# ATLAS_XP2V5_Sheet_5.net
KiCad netlist of a schematic drawn in Altium Designer
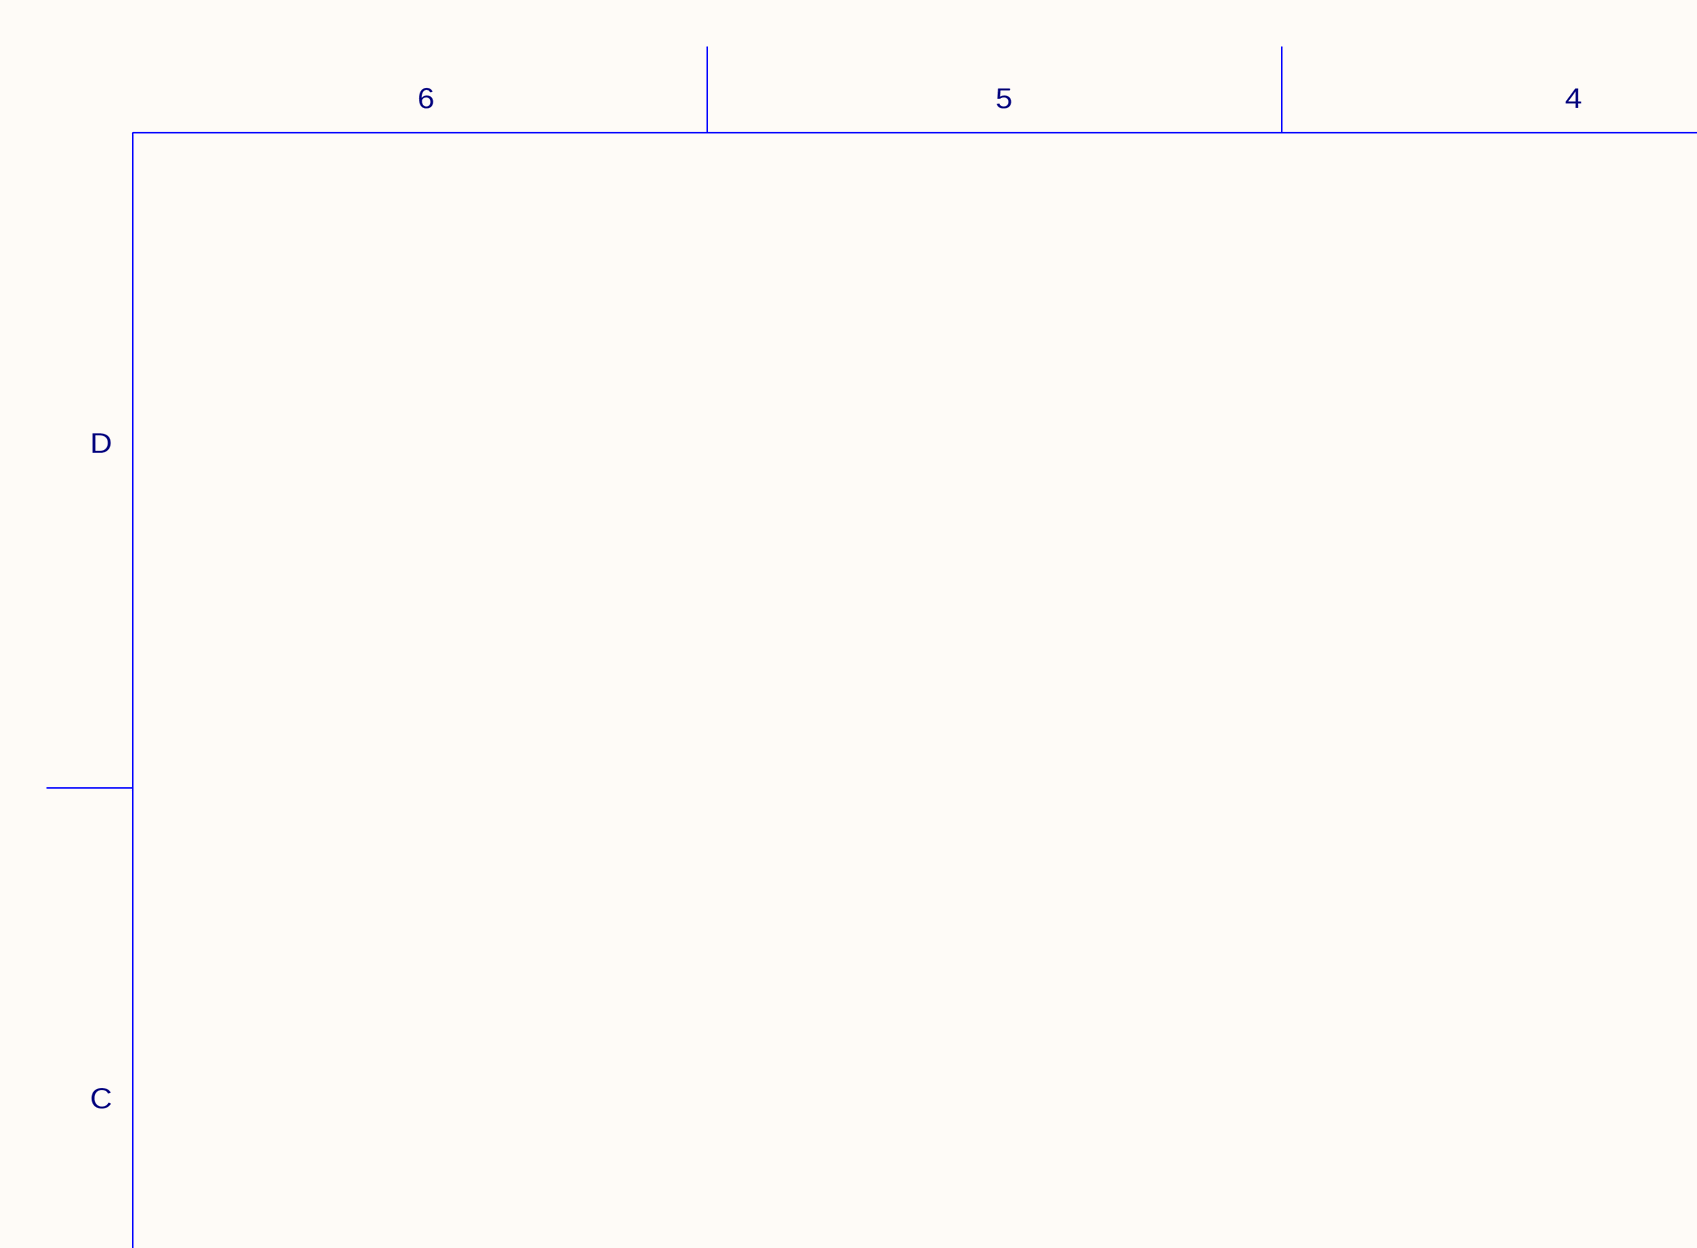
[diagram p0: ATLAS_XP2V5.Sheet 5.SchDoc, top left]
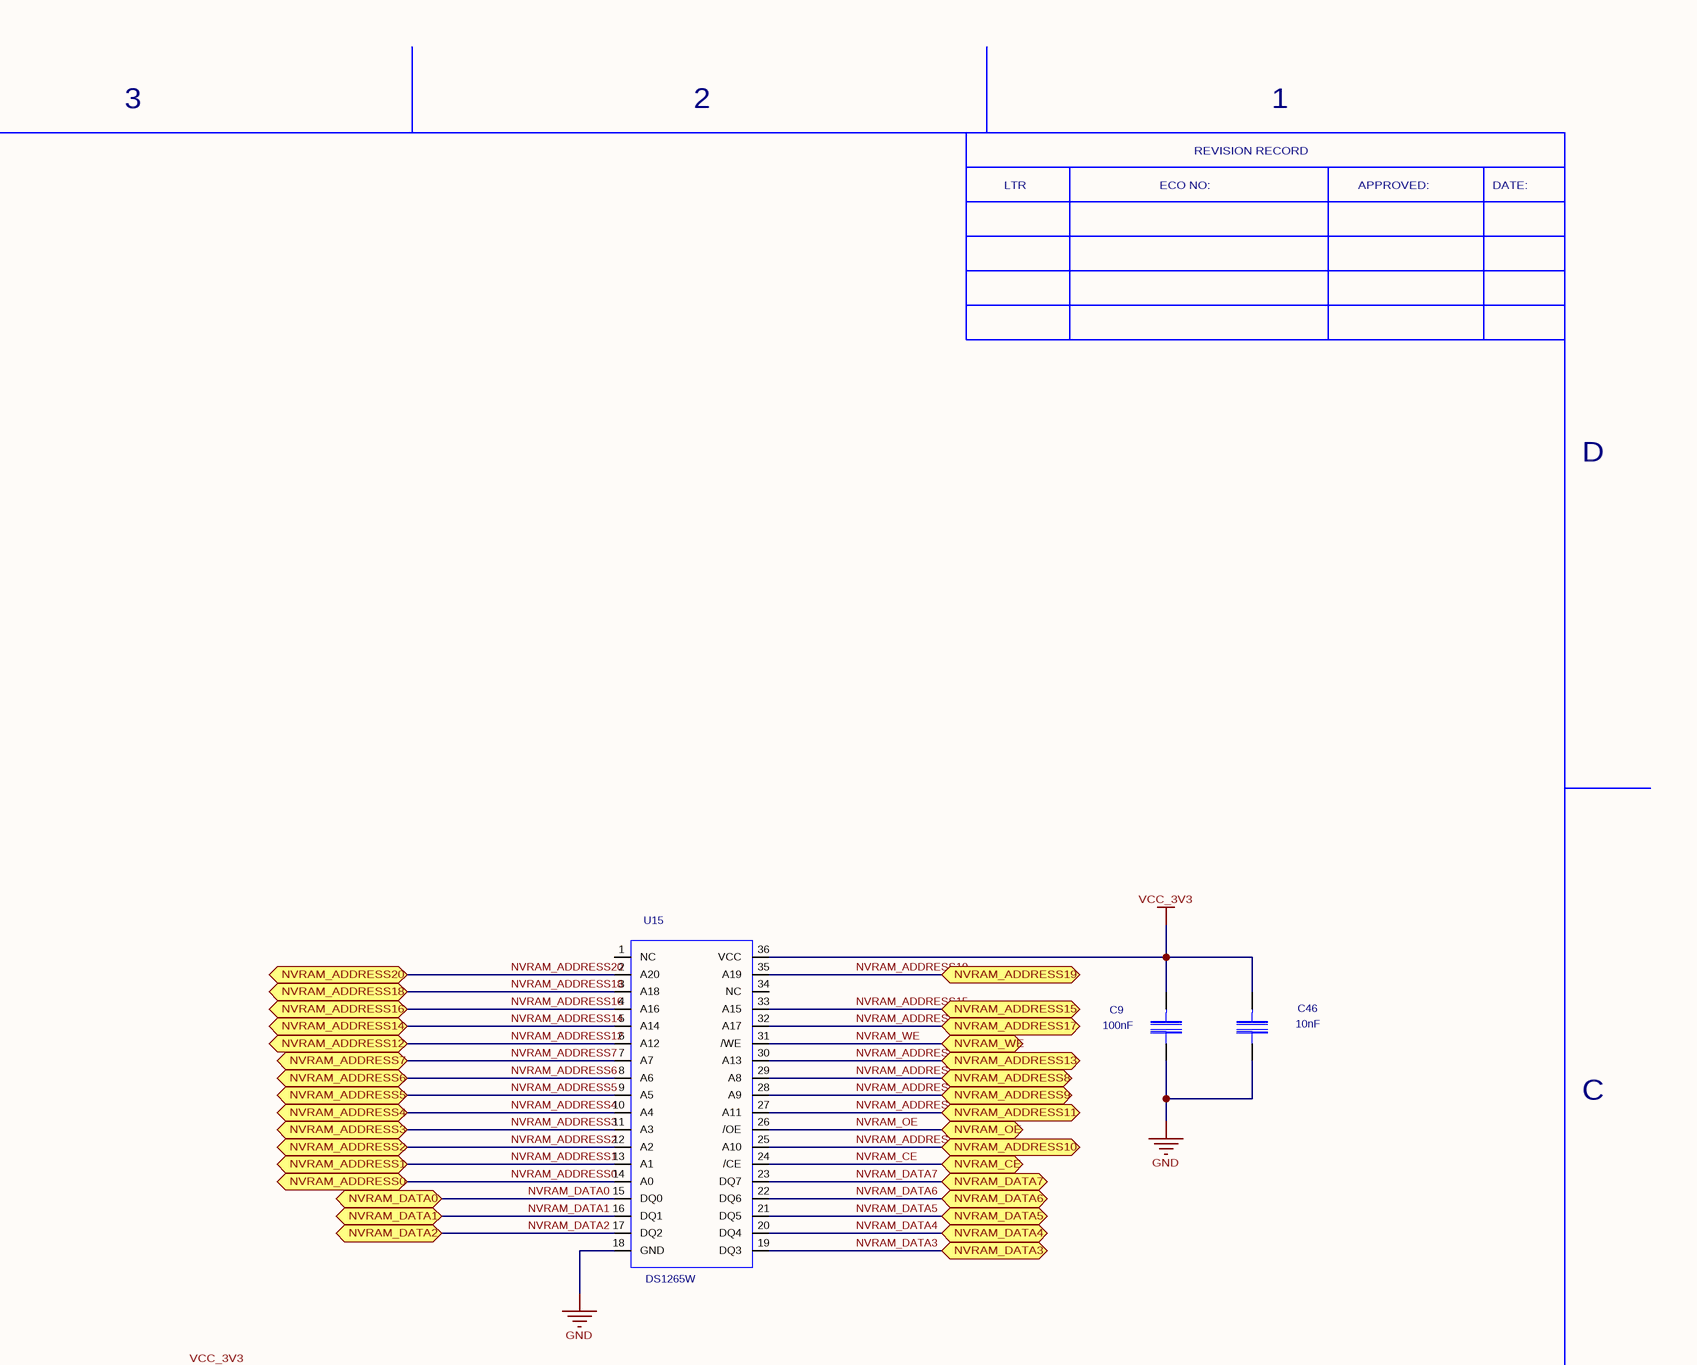
[diagram p1: ATLAS_XP2V5.Sheet 5.SchDoc, top right]
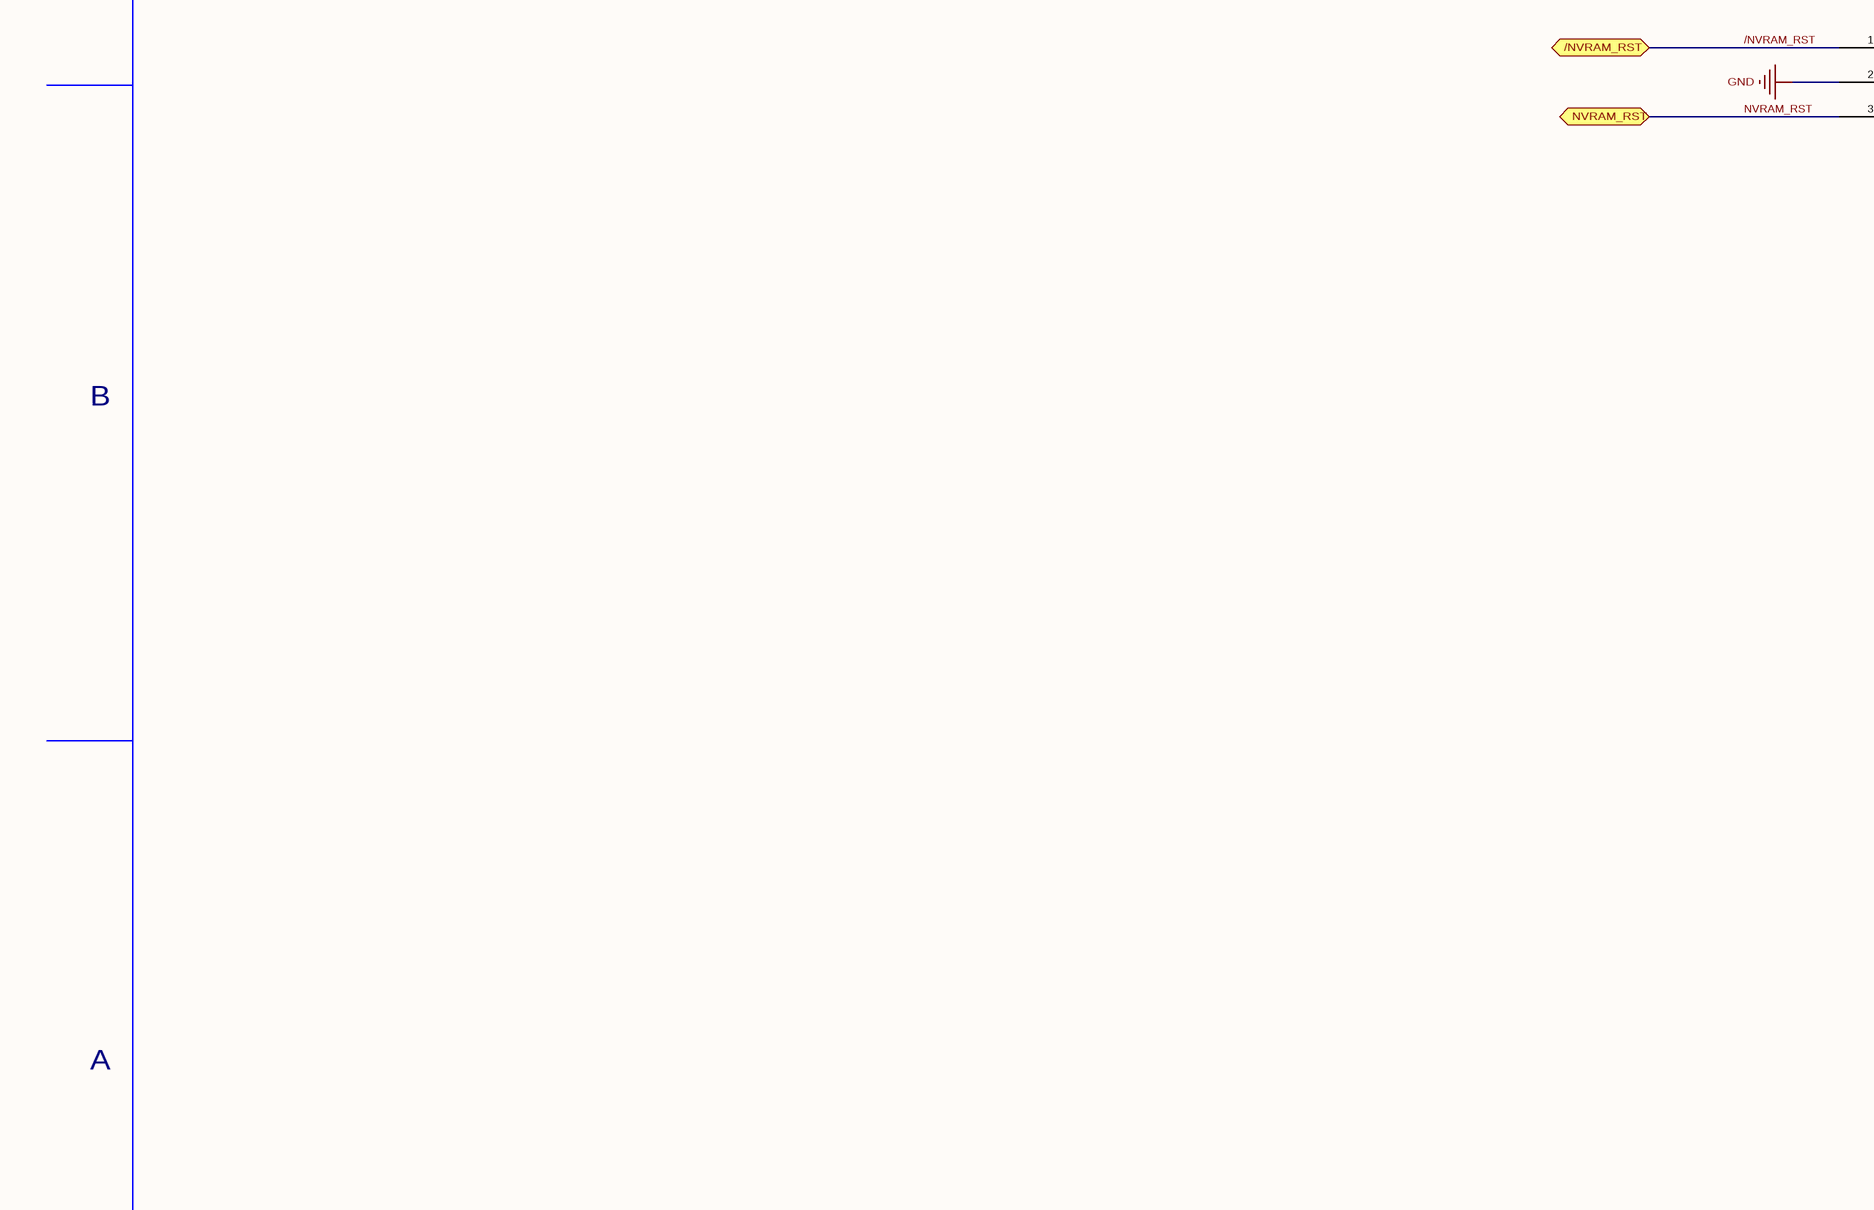
[diagram p2: ATLAS_XP2V5.Sheet 5.SchDoc, bottom left]
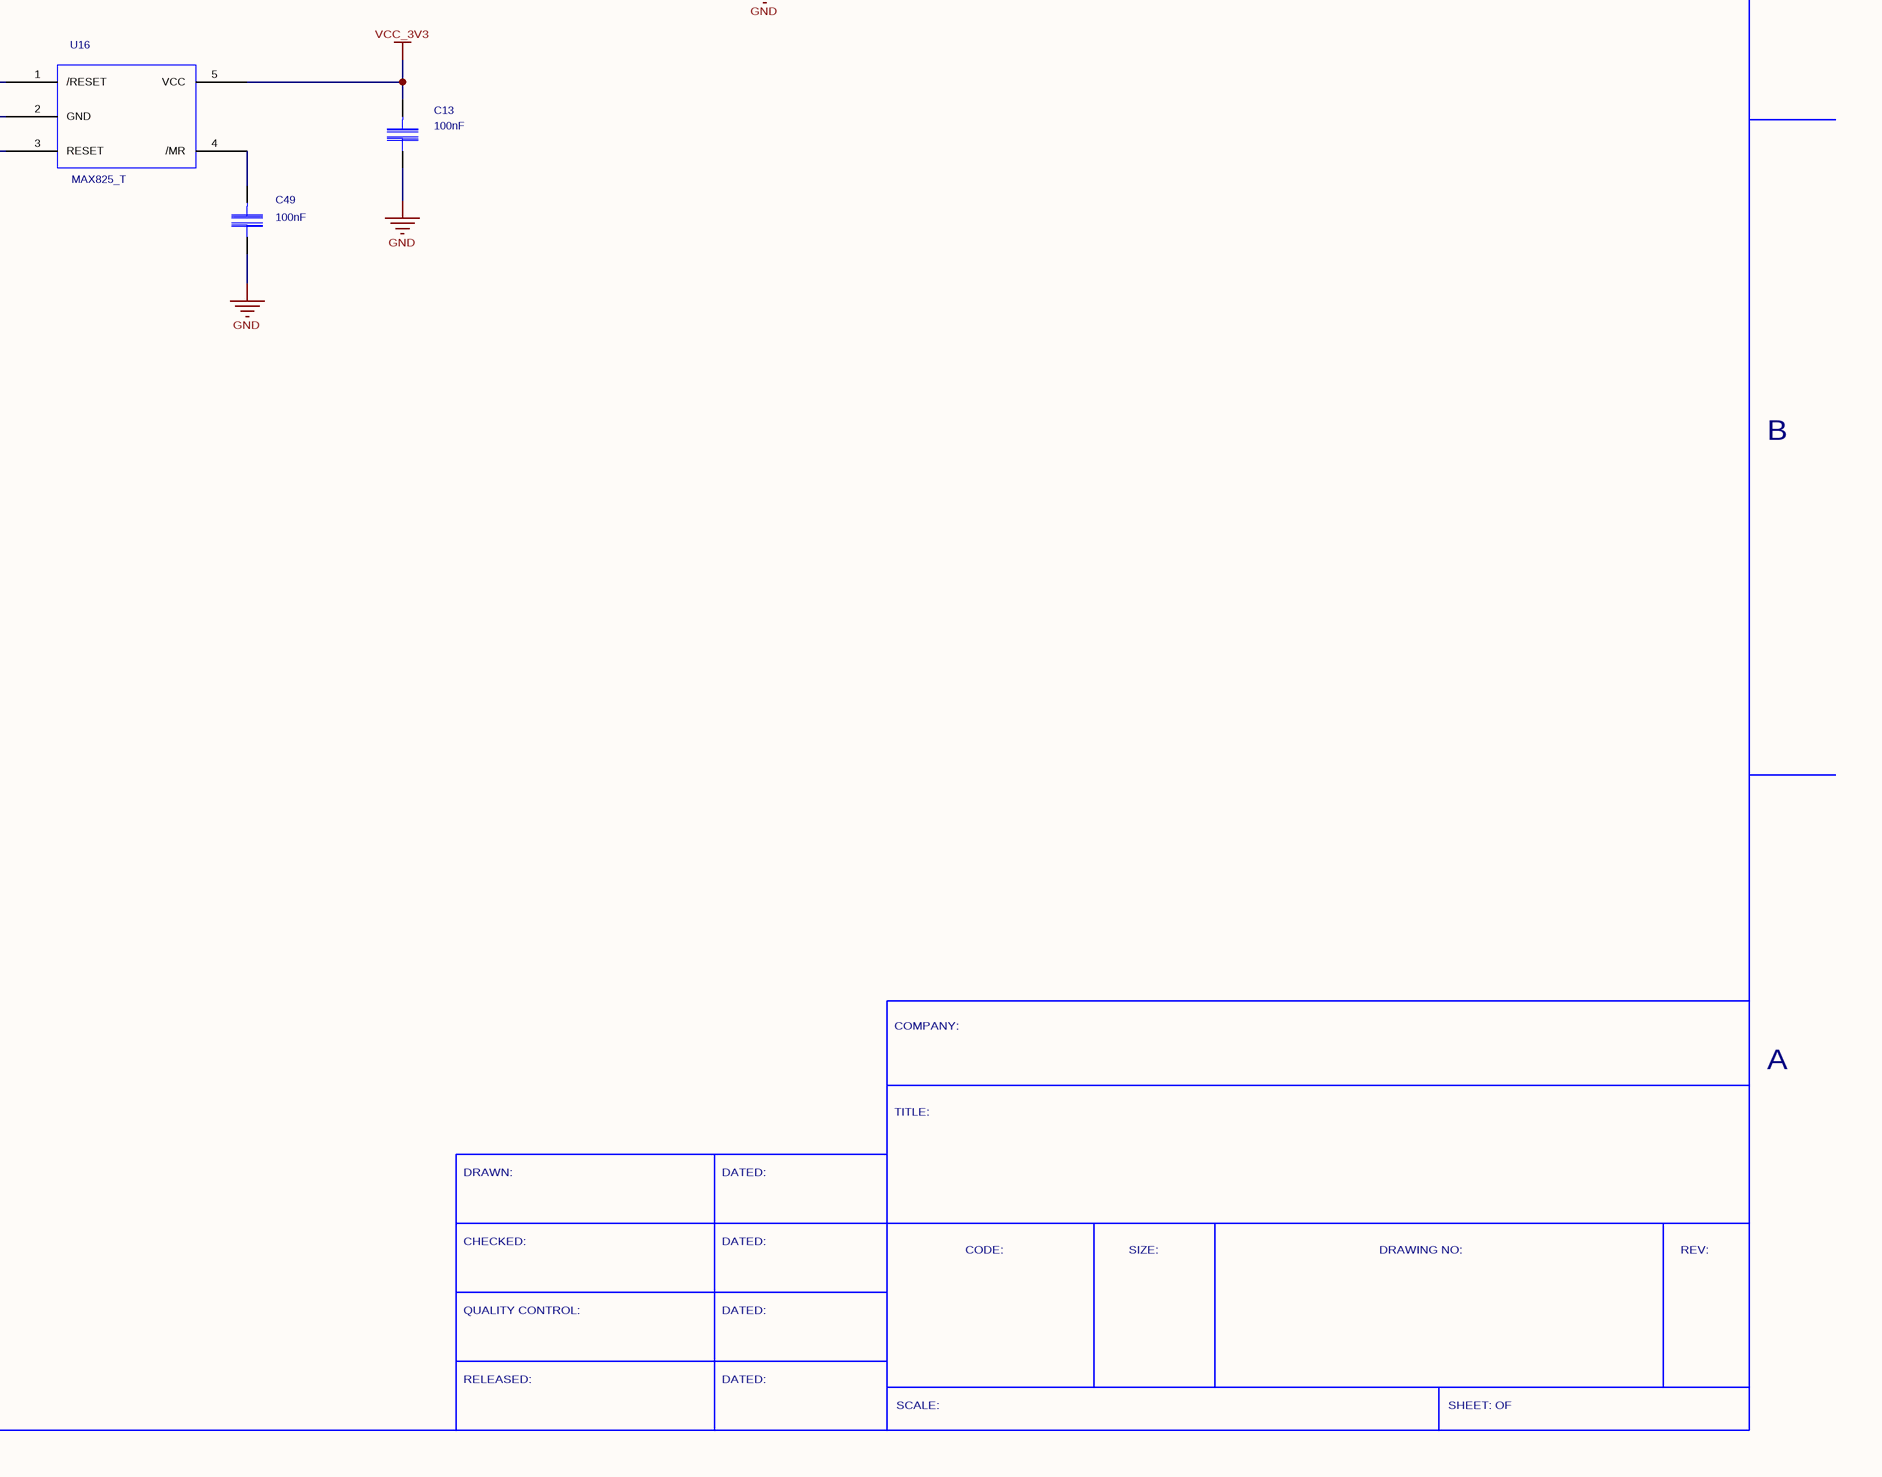
[diagram p3: ATLAS_XP2V5.Sheet 5.SchDoc, bottom right]

(export (version "E")
  (design (tool "Eeschema 10.0.6"))
  (components
    (comp (ref "C9")
      (value "100nF")
      (footprint "SM/C_0805")
      (fields (field (name "Comment") "C"))
      (libsource (lib "*") (part "C"))
    )
    (comp (ref "C13")
      (value "100nF")
      (footprint "SM/C_0805")
      (fields (field (name "Comment") "C"))
      (libsource (lib "*") (part "C"))
    )
    (comp (ref "C46")
      (value "10nF")
      (footprint "SM/C_0805")
      (fields (field (name "Comment") "C"))
      (libsource (lib "*") (part "C"))
    )
    (comp (ref "C49")
      (value "100nF")
      (footprint "SM/C_0805")
      (fields (field (name "Comment") "C"))
      (libsource (lib "*") (part "C"))
    )
    (comp (ref "U15")
      (value "DS1265W")
      (footprint "DIP.100/36/W.600/L1.850")
      (libsource (lib "*") (part "DS1265W"))
    )
    (comp (ref "U16")
      (value "MAX825_T")
      (footprint "SOT23_5_MILOS_REV4")
      (libsource (lib "*") (part "MAX825_T"))
    )
  )
  (nets
    (net (code "1") (name "/NVRAM_ADDRESS0") (class "Default")
      (node (ref "U15") (pin "14") (pinfunction "A0_14") (pintype "passive"))
    )
    (net (code "2") (name "/NVRAM_ADDRESS1") (class "Default")
      (node (ref "U15") (pin "13") (pinfunction "A1_13") (pintype "passive"))
    )
    (net (code "3") (name "/NVRAM_ADDRESS2") (class "Default")
      (node (ref "U15") (pin "12") (pinfunction "A2_12") (pintype "passive"))
    )
    (net (code "4") (name "/NVRAM_ADDRESS3") (class "Default")
      (node (ref "U15") (pin "11") (pinfunction "A3_11") (pintype "passive"))
    )
    (net (code "5") (name "/NVRAM_ADDRESS4") (class "Default")
      (node (ref "U15") (pin "10") (pinfunction "A4_10") (pintype "passive"))
    )
    (net (code "6") (name "/NVRAM_ADDRESS5") (class "Default")
      (node (ref "U15") (pin "9") (pinfunction "A5_9") (pintype "passive"))
    )
    (net (code "7") (name "/NVRAM_ADDRESS6") (class "Default")
      (node (ref "U15") (pin "8") (pinfunction "A6_8") (pintype "passive"))
    )
    (net (code "8") (name "/NVRAM_ADDRESS7") (class "Default")
      (node (ref "U15") (pin "7") (pinfunction "A7_7") (pintype "passive"))
    )
    (net (code "9") (name "/NVRAM_ADDRESS8") (class "Default")
      (node (ref "U15") (pin "29") (pinfunction "A8_29") (pintype "passive"))
    )
    (net (code "10") (name "/NVRAM_ADDRESS9") (class "Default")
      (node (ref "U15") (pin "28") (pinfunction "A9_28") (pintype "passive"))
    )
    (net (code "11") (name "/NVRAM_ADDRESS10") (class "Default")
      (node (ref "U15") (pin "25") (pinfunction "A10_25") (pintype "passive"))
    )
    (net (code "12") (name "/NVRAM_ADDRESS11") (class "Default")
      (node (ref "U15") (pin "27") (pinfunction "A11_27") (pintype "passive"))
    )
    (net (code "13") (name "/NVRAM_ADDRESS12") (class "Default")
      (node (ref "U15") (pin "6") (pinfunction "A12_6") (pintype "passive"))
    )
    (net (code "14") (name "/NVRAM_ADDRESS13") (class "Default")
      (node (ref "U15") (pin "30") (pinfunction "A13_30") (pintype "passive"))
    )
    (net (code "15") (name "/NVRAM_ADDRESS14") (class "Default")
      (node (ref "U15") (pin "5") (pinfunction "A14_5") (pintype "passive"))
    )
    (net (code "16") (name "/NVRAM_ADDRESS15") (class "Default")
      (node (ref "U15") (pin "33") (pinfunction "A15_33") (pintype "passive"))
    )
    (net (code "17") (name "/NVRAM_ADDRESS16") (class "Default")
      (node (ref "U15") (pin "4") (pinfunction "A16_4") (pintype "passive"))
    )
    (net (code "18") (name "/NVRAM_ADDRESS17") (class "Default")
      (node (ref "U15") (pin "32") (pinfunction "A17_32") (pintype "passive"))
    )
    (net (code "19") (name "/NVRAM_ADDRESS18") (class "Default")
      (node (ref "U15") (pin "3") (pinfunction "A18_3") (pintype "passive"))
    )
    (net (code "20") (name "/NVRAM_ADDRESS19") (class "Default")
      (node (ref "U15") (pin "35") (pinfunction "A19_35") (pintype "passive"))
    )
    (net (code "21") (name "/NVRAM_ADDRESS20") (class "Default")
      (node (ref "U15") (pin "2") (pinfunction "A20_2") (pintype "passive"))
    )
    (net (code "22") (name "/NVRAM_CE") (class "Default")
      (node (ref "U15") (pin "24") (pinfunction "/CE_24") (pintype "passive"))
    )
    (net (code "23") (name "/NVRAM_DATA0") (class "Default")
      (node (ref "U15") (pin "15") (pinfunction "DQ0_15") (pintype "bidirectional"))
    )
    (net (code "24") (name "/NVRAM_DATA1") (class "Default")
      (node (ref "U15") (pin "16") (pinfunction "DQ1_16") (pintype "bidirectional"))
    )
    (net (code "25") (name "/NVRAM_DATA2") (class "Default")
      (node (ref "U15") (pin "17") (pinfunction "DQ2_17") (pintype "bidirectional"))
    )
    (net (code "26") (name "/NVRAM_DATA3") (class "Default")
      (node (ref "U15") (pin "19") (pinfunction "DQ3_19") (pintype "bidirectional"))
    )
    (net (code "27") (name "/NVRAM_DATA4") (class "Default")
      (node (ref "U15") (pin "20") (pinfunction "DQ4_20") (pintype "bidirectional"))
    )
    (net (code "28") (name "/NVRAM_DATA5") (class "Default")
      (node (ref "U15") (pin "21") (pinfunction "DQ5_21") (pintype "bidirectional"))
    )
    (net (code "29") (name "/NVRAM_DATA6") (class "Default")
      (node (ref "U15") (pin "22") (pinfunction "DQ6_22") (pintype "bidirectional"))
    )
    (net (code "30") (name "/NVRAM_DATA7") (class "Default")
      (node (ref "U15") (pin "23") (pinfunction "DQ7_23") (pintype "bidirectional"))
    )
    (net (code "31") (name "/NVRAM_OE") (class "Default")
      (node (ref "U15") (pin "26") (pinfunction "/OE_26") (pintype "passive"))
    )
    (net (code "32") (name "/NVRAM_RST") (class "Default")
      (node (ref "U16") (pin "3") (pinfunction "RESET_3") (pintype "passive"))
    )
    (net (code "33") (name "/NVRAM_WE") (class "Default")
      (node (ref "U15") (pin "31") (pinfunction "/WE_31") (pintype "passive"))
    )
    (net (code "34") (name "/{slash}NVRAM_RST") (class "Default")
      (node (ref "U16") (pin "1") (pinfunction "/RESET_1") (pintype "passive"))
    )
    (net (code "35") (name "GND") (class "Default")
      (node (ref "C13") (pin "2") (pinfunction "2_2") (pintype "passive"))
      (node (ref "C46") (pin "2") (pinfunction "2_2") (pintype "passive"))
      (node (ref "C49") (pin "2") (pinfunction "2_2") (pintype "passive"))
      (node (ref "C9") (pin "2") (pinfunction "2_2") (pintype "passive"))
      (node (ref "U15") (pin "18") (pinfunction "GND_18") (pintype "power_in"))
      (node (ref "U16") (pin "2") (pinfunction "GND_2") (pintype "power_in"))
    )
    (net (code "36") (name "Net-(U16-{slash}MR)") (class "Default")
      (node (ref "C49") (pin "1") (pinfunction "1_1") (pintype "passive"))
      (node (ref "U16") (pin "4") (pinfunction "/MR_4") (pintype "passive"))
    )
    (net (code "37") (name "VCC_3V3") (class "Default")
      (node (ref "C13") (pin "1") (pinfunction "1_1") (pintype "passive"))
      (node (ref "C46") (pin "1") (pinfunction "1_1") (pintype "passive"))
      (node (ref "C9") (pin "1") (pinfunction "1_1") (pintype "passive"))
      (node (ref "U15") (pin "36") (pinfunction "VCC_36") (pintype "power_in"))
      (node (ref "U16") (pin "5") (pinfunction "VCC_5") (pintype "power_in"))
    )
    (net (code "38") (name "unconnected-(U15-NC-Pad1)") (class "Default")
      (node (ref "U15") (pin "1") (pinfunction "NC_1") (pintype "passive"))
    )
    (net (code "39") (name "unconnected-(U15-NC-Pad34)") (class "Default")
      (node (ref "U15") (pin "34") (pinfunction "NC_34") (pintype "passive"))
    )
  )
)
